# attinier84-2digit-shield-mk-2_0.net
KiCad netlist of a schematic drawn in EAGLE
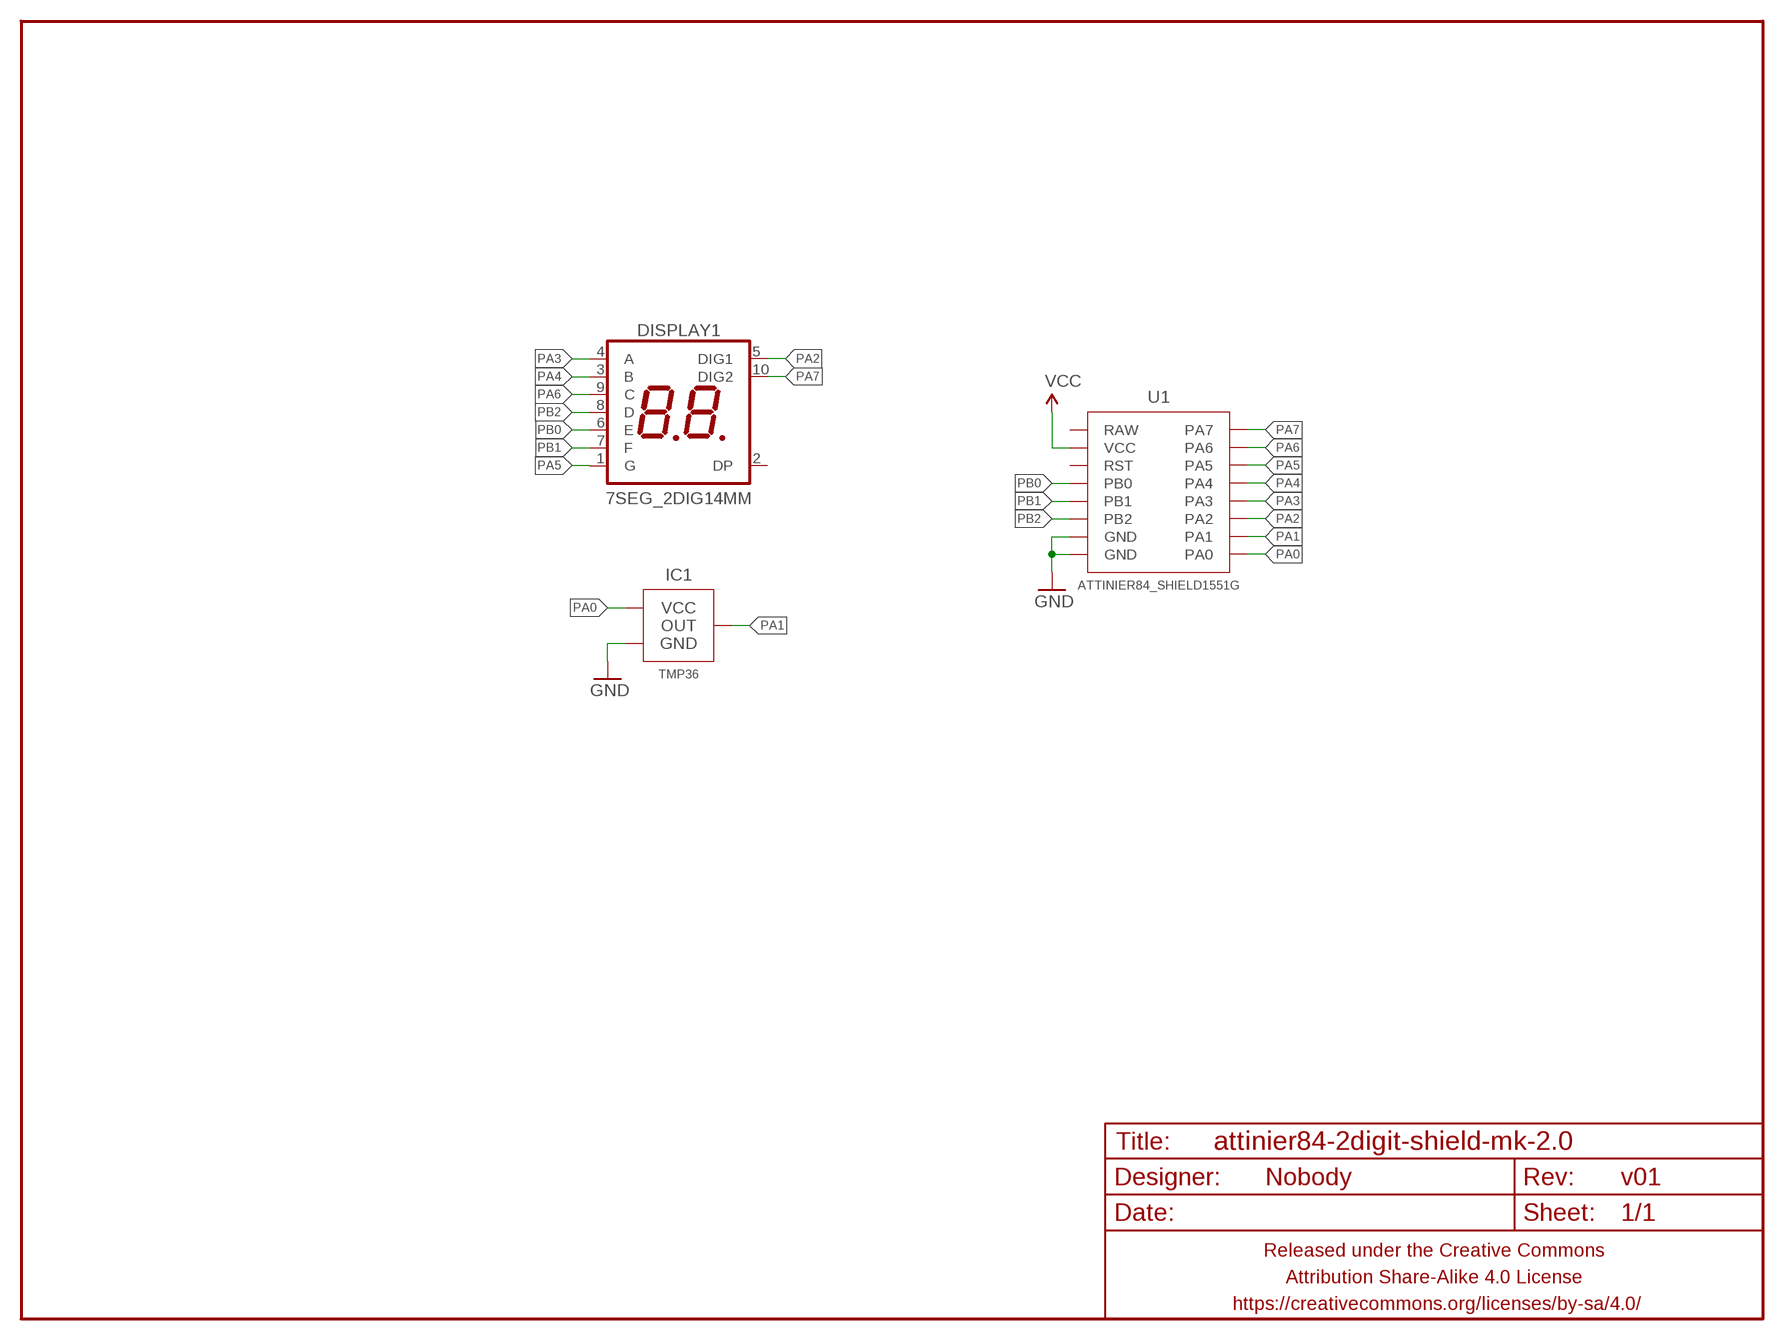
[diagram p0: schematic, sheet 1]

(export (version "E")
  (design (tool "Eeschema 10.0.6"))
  (components
    (comp (ref "DISPLAY1")
      (value "7SEG_2DIG14MM")
      (footprint "eagle-import:7SEG_2DIG_14MM")
      (libsource (lib "eagle-import") (part "7SEG_2DIG14MM"))
    )
    (comp (ref "FRAME1")
      (value "FRAME-LETTERNO_PACKAGE")
      (footprint "eagle-import:DUMMY")
      (fields (field (name "DESIGNER") "Nobody"))
      (libsource (lib "eagle-import") (part "FRAME-LETTERNO_PACKAGE"))
    )
    (comp (ref "IC1")
      (value "TMP36")
      (footprint "eagle-import:TO-92-AMMO")
      (libsource (lib "eagle-import") (part "TMP36TO-92"))
    )
    (comp (ref "U1")
      (value "ATTINIER84_SHIELD1551G")
      (footprint "eagle-import:ATTINIER84_SHIELD2")
      (libsource (lib "eagle-import") (part "ATTINIER84_SHIELD1551G"))
    )
  )
  (nets
    (net (code "1") (name "GND") (class "Default")
      (node (ref "IC1") (pin "3") (pinfunction "GND_3") (pintype "bidirectional"))
      (node (ref "U1") (pin "GND@1") (pinfunction "GND_GND@1") (pintype "bidirectional"))
      (node (ref "U1") (pin "GND@2") (pinfunction "GND_GND@2") (pintype "bidirectional"))
    )
    (net (code "2") (name "PA0") (class "Default")
      (node (ref "IC1") (pin "1") (pinfunction "VCC_1") (pintype "bidirectional"))
      (node (ref "U1") (pin "PA0") (pinfunction "PA0_PA0") (pintype "bidirectional"))
    )
    (net (code "3") (name "PA1") (class "Default")
      (node (ref "IC1") (pin "2") (pinfunction "OUT_2") (pintype "bidirectional"))
      (node (ref "U1") (pin "PA1") (pinfunction "PA1_PA1") (pintype "bidirectional"))
    )
    (net (code "4") (name "PA2") (class "Default")
      (node (ref "DISPLAY1") (pin "5") (pinfunction "DIG1_5") (pintype "passive"))
      (node (ref "U1") (pin "PA2") (pinfunction "PA2_PA2") (pintype "bidirectional"))
    )
    (net (code "5") (name "PA3") (class "Default")
      (node (ref "DISPLAY1") (pin "4") (pinfunction "A_4") (pintype "passive"))
      (node (ref "U1") (pin "PA3") (pinfunction "PA3_PA3") (pintype "bidirectional"))
    )
    (net (code "6") (name "PA4") (class "Default")
      (node (ref "DISPLAY1") (pin "3") (pinfunction "B_3") (pintype "passive"))
      (node (ref "U1") (pin "PA4") (pinfunction "PA4_PA4") (pintype "bidirectional"))
    )
    (net (code "7") (name "PA5") (class "Default")
      (node (ref "DISPLAY1") (pin "1") (pinfunction "G_1") (pintype "passive"))
      (node (ref "U1") (pin "PA5") (pinfunction "PA5_PA5") (pintype "bidirectional"))
    )
    (net (code "8") (name "PA6") (class "Default")
      (node (ref "DISPLAY1") (pin "9") (pinfunction "C_9") (pintype "passive"))
      (node (ref "U1") (pin "PA6") (pinfunction "PA6_PA6") (pintype "bidirectional"))
    )
    (net (code "9") (name "PA7") (class "Default")
      (node (ref "DISPLAY1") (pin "10") (pinfunction "DIG2_10") (pintype "passive"))
      (node (ref "U1") (pin "PA7") (pinfunction "PA7_PA7") (pintype "bidirectional"))
    )
    (net (code "10") (name "PB0") (class "Default")
      (node (ref "DISPLAY1") (pin "6") (pinfunction "E_6") (pintype "passive"))
      (node (ref "U1") (pin "PB0") (pinfunction "PB0_PB0") (pintype "bidirectional"))
    )
    (net (code "11") (name "PB1") (class "Default")
      (node (ref "DISPLAY1") (pin "7") (pinfunction "F_7") (pintype "passive"))
      (node (ref "U1") (pin "PB1") (pinfunction "PB1_PB1") (pintype "bidirectional"))
    )
    (net (code "12") (name "PB2") (class "Default")
      (node (ref "DISPLAY1") (pin "8") (pinfunction "D_8") (pintype "passive"))
      (node (ref "U1") (pin "PB2") (pinfunction "PB2_PB2") (pintype "bidirectional"))
    )
    (net (code "13") (name "VCC") (class "Default")
      (node (ref "U1") (pin "VCC") (pinfunction "VCC_VCC") (pintype "bidirectional"))
    )
    (net (code "14") (name "unconnected-(DISPLAY1-DP-Pad2)") (class "Default")
      (node (ref "DISPLAY1") (pin "2") (pinfunction "DP_2") (pintype "passive"))
    )
    (net (code "15") (name "unconnected-(U1-PadRAW)") (class "Default")
      (node (ref "U1") (pin "RAW") (pinfunction "RAW_RAW") (pintype "bidirectional"))
    )
    (net (code "16") (name "unconnected-(U1-PadRST)") (class "Default")
      (node (ref "U1") (pin "RST") (pinfunction "RST_RST") (pintype "bidirectional"))
    )
  )
)
